# lm324.net
KiCad netlist of a schematic drawn in EAGLE
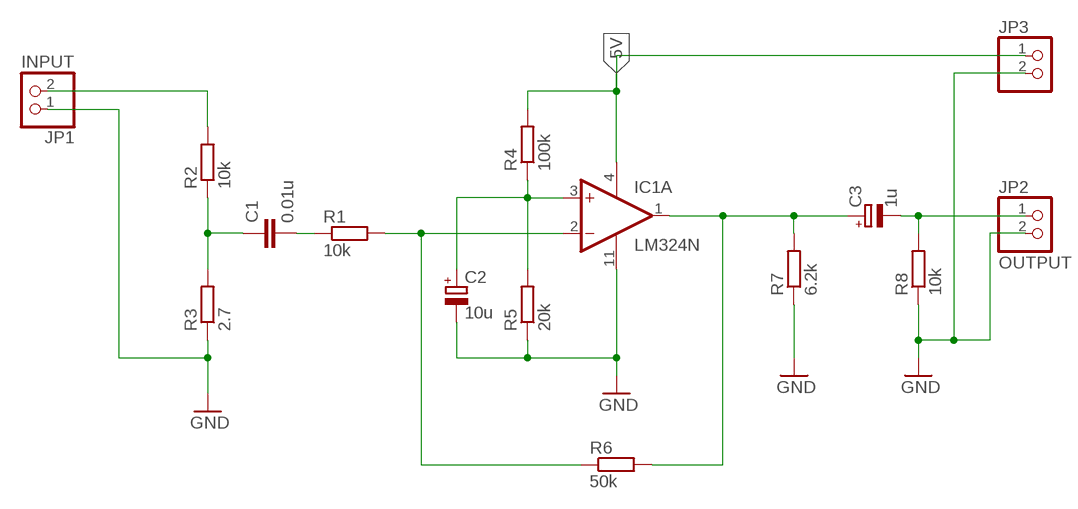
[diagram p0: schematic, sheet 1]

(export (version "E")
  (design (tool "Eeschema 10.0.6"))
  (components
    (comp (ref "C1")
      (value "0.01u")
      (footprint "eagle-import:C0805")
      (libsource (lib "eagle-import") (part "C-EUC0805"))
    )
    (comp (ref "C2")
      (value "10u")
      (footprint "eagle-import:E3,5-8")
      (libsource (lib "eagle-import") (part "CPOL-EUE3.5-8"))
    )
    (comp (ref "C3")
      (value "1u")
      (footprint "eagle-import:E3,5-8")
      (libsource (lib "eagle-import") (part "CPOL-EUE3.5-8"))
    )
    (comp (ref "IC1")
      (value "LM324N")
      (footprint "eagle-import:DIL14")
      (libsource (lib "eagle-import") (part "LM324N"))
    )
    (comp (ref "JP1")
      (value "INPUT")
      (footprint "eagle-import:1X02")
      (libsource (lib "eagle-import") (part "PINHD-1X2"))
    )
    (comp (ref "JP2")
      (value "OUTPUT")
      (footprint "eagle-import:1X02")
      (libsource (lib "eagle-import") (part "PINHD-1X2"))
    )
    (comp (ref "JP3")
      (value "PINHD-1X2")
      (footprint "eagle-import:1X02")
      (libsource (lib "eagle-import") (part "PINHD-1X2"))
    )
    (comp (ref "R1")
      (value "10k")
      (footprint "eagle-import:R0805")
      (libsource (lib "eagle-import") (part "R-EU_R0805"))
    )
    (comp (ref "R2")
      (value "10k")
      (footprint "eagle-import:R0805")
      (libsource (lib "eagle-import") (part "R-EU_R0805"))
    )
    (comp (ref "R3")
      (value "2.7")
      (footprint "eagle-import:R0805")
      (libsource (lib "eagle-import") (part "R-EU_R0805"))
    )
    (comp (ref "R4")
      (value "100k")
      (footprint "eagle-import:R0805")
      (libsource (lib "eagle-import") (part "R-EU_R0805"))
    )
    (comp (ref "R5")
      (value "20k")
      (footprint "eagle-import:R0805")
      (libsource (lib "eagle-import") (part "R-EU_R0805"))
    )
    (comp (ref "R6")
      (value "50k")
      (footprint "eagle-import:R0805")
      (libsource (lib "eagle-import") (part "R-EU_R0805"))
    )
    (comp (ref "R7")
      (value "6.2k")
      (footprint "eagle-import:R0805")
      (libsource (lib "eagle-import") (part "R-EU_R0805"))
    )
    (comp (ref "R8")
      (value "10k")
      (footprint "eagle-import:R0805")
      (libsource (lib "eagle-import") (part "R-EU_R0805"))
    )
  )
  (nets
    (net (code "1") (name "5V") (class "Default")
      (node (ref "IC1") (pin "4") (pinfunction "V+_4") (pintype "power_in"))
      (node (ref "JP3") (pin "1") (pinfunction "1_1") (pintype "passive"))
      (node (ref "R4") (pin "2") (pinfunction "2_2") (pintype "passive"))
    )
    (net (code "2") (name "GND") (class "Default")
      (node (ref "C2") (pin "-") (pinfunction "-_-") (pintype "passive"))
      (node (ref "IC1") (pin "11") (pinfunction "V-_11") (pintype "power_in"))
      (node (ref "JP1") (pin "1") (pinfunction "1_1") (pintype "passive"))
      (node (ref "JP2") (pin "2") (pinfunction "2_2") (pintype "passive"))
      (node (ref "JP3") (pin "2") (pinfunction "2_2") (pintype "passive"))
      (node (ref "R3") (pin "1") (pinfunction "1_1") (pintype "passive"))
      (node (ref "R5") (pin "1") (pinfunction "1_1") (pintype "passive"))
      (node (ref "R7") (pin "1") (pinfunction "1_1") (pintype "passive"))
      (node (ref "R8") (pin "1") (pinfunction "1_1") (pintype "passive"))
    )
    (net (code "3") (name "Net-(C1-Pad1)") (class "Default")
      (node (ref "C1") (pin "1") (pinfunction "1_1") (pintype "passive"))
      (node (ref "R2") (pin "1") (pinfunction "1_1") (pintype "passive"))
      (node (ref "R3") (pin "2") (pinfunction "2_2") (pintype "passive"))
    )
    (net (code "4") (name "Net-(C1-Pad2)") (class "Default")
      (node (ref "C1") (pin "2") (pinfunction "2_2") (pintype "passive"))
      (node (ref "R1") (pin "1") (pinfunction "1_1") (pintype "passive"))
    )
    (net (code "5") (name "Net-(C3-Pad-)") (class "Default")
      (node (ref "C3") (pin "-") (pinfunction "-_-") (pintype "passive"))
      (node (ref "JP2") (pin "1") (pinfunction "1_1") (pintype "passive"))
      (node (ref "R8") (pin "2") (pinfunction "2_2") (pintype "passive"))
    )
    (net (code "6") (name "Net-(IC1A-+IN)") (class "Default")
      (node (ref "C2") (pin "+") (pinfunction "+_+") (pintype "passive"))
      (node (ref "IC1") (pin "3") (pinfunction "+IN_3") (pintype "input"))
      (node (ref "R4") (pin "1") (pinfunction "1_1") (pintype "passive"))
      (node (ref "R5") (pin "2") (pinfunction "2_2") (pintype "passive"))
    )
    (net (code "7") (name "Net-(IC1A--IN)") (class "Default")
      (node (ref "IC1") (pin "2") (pinfunction "-IN_2") (pintype "input"))
      (node (ref "R1") (pin "2") (pinfunction "2_2") (pintype "passive"))
      (node (ref "R6") (pin "1") (pinfunction "1_1") (pintype "passive"))
    )
    (net (code "8") (name "Net-(IC1A-OUT)") (class "Default")
      (node (ref "C3") (pin "+") (pinfunction "+_+") (pintype "passive"))
      (node (ref "IC1") (pin "1") (pinfunction "OUT_1") (pintype "output"))
      (node (ref "R6") (pin "2") (pinfunction "2_2") (pintype "passive"))
      (node (ref "R7") (pin "2") (pinfunction "2_2") (pintype "passive"))
    )
    (net (code "9") (name "Net-(JP1-Pad2)") (class "Default")
      (node (ref "JP1") (pin "2") (pinfunction "2_2") (pintype "passive"))
      (node (ref "R2") (pin "2") (pinfunction "2_2") (pintype "passive"))
    )
  )
)
